# Assignment4B-IR-Sensor_Schematic.net
KiCad netlist of a schematic drawn in EAGLE
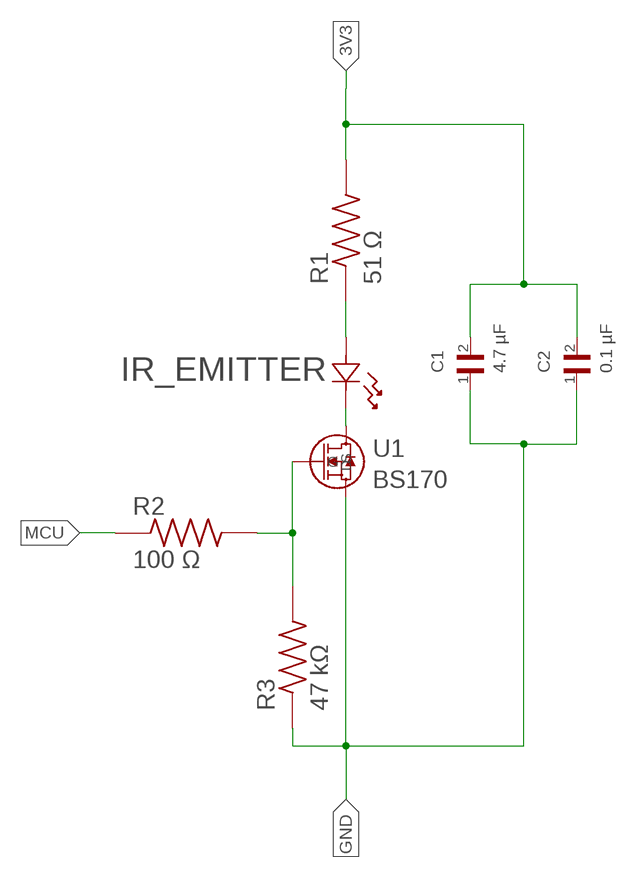
[diagram p0: schematic, sheet 1]

(export (version "E")
  (design (tool "Eeschema 10.0.6"))
  (components
    (comp (ref "C1")
      (value "4.7 µF")
      (footprint "eagle-import:CAPC2012X140N")
      (fields
        (field (name "DIGIKEY_PART_NUMBER") "490-14466-2-ND")
        (field (name "MF") "Murata Electronics")
        (field (name "MP") "GRM21BR71C475KE51L")
      )
      (libsource (lib "eagle-import") (part "GRM21BR71C475KE51L"))
    )
    (comp (ref "C2")
      (value "0.1 µF")
      (footprint "eagle-import:CAPC2012X140N")
      (fields (field (name "MF") "Murata") (field (name "MP") "GCM21BR72A104KA37K"))
      (libsource (lib "eagle-import") (part "GCM21BR72A104KA37K"))
    )
    (comp (ref "LED1")
      (value "IR_EMITTER")
      (footprint "eagle-import:LED_INL-5AMIR15_INO")
      (fields
        (field (name "MANUFACTURER_PART_NUMBER") "INL-5AMIR15")
        (field (name "COPYRIGHT") "Copyright (C) 2024 Ultra Librarian. All rights reserved.")
      )
      (libsource (lib "eagle-import") (part "INL-5AMIR15"))
    )
    (comp (ref "R1")
      (value "51 Ω")
      (footprint "eagle-import:RESC2012X60N")
      (fields
        (field (name "DIGIKEY_PART_NUMBER") "541-51.0TTR-ND")
        (field (name "MF") "Vishay")
        (field (name "MP") "CRCW080551R0FKEAHP")
      )
      (libsource (lib "eagle-import") (part "CRCW080551R0FKEAHP"))
    )
    (comp (ref "R2")
      (value "100 Ω")
      (footprint "eagle-import:RESC2012X60N")
      (fields
        (field (name "DIGIKEY_PART_NUMBER") "541-100TTR-ND")
        (field (name "MF") "Vishay")
        (field (name "MP") "CRCW0805100RFKEAHP")
      )
      (libsource (lib "eagle-import") (part "CRCW0805100RFKEAHP"))
    )
    (comp (ref "R3")
      (value "47 kΩ")
      (footprint "eagle-import:RESC2012X50N")
      (fields
        (field (name "DIGIKEY_PART_NUMBER") "541-47KATR-ND")
        (field (name "MF") "Vishay Dale")
        (field (name "MP") "CRCW080547K0JNEA")
      )
      (libsource (lib "eagle-import") (part "CRCW080547K0JNEA"))
    )
    (comp (ref "U1")
      (value "BS170")
      (footprint "eagle-import:TO_SA06_ONS")
      (fields (field (name "COPYRIGHT") "Copyright (C) 2024 Ultra Librarian. All rights reserved."))
      (libsource (lib "eagle-import") (part "BS170"))
    )
  )
  (nets
    (net (code "1") (name "3V3") (class "Default")
      (node (ref "C1") (pin "2") (pinfunction "2_2") (pintype "passive"))
      (node (ref "C2") (pin "2") (pinfunction "2_2") (pintype "passive"))
      (node (ref "R1") (pin "2") (pinfunction "2_2") (pintype "passive"))
    )
    (net (code "2") (name "GND") (class "Default")
      (node (ref "C1") (pin "1") (pinfunction "1_1") (pintype "passive"))
      (node (ref "C2") (pin "1") (pinfunction "1_1") (pintype "passive"))
      (node (ref "R3") (pin "1") (pinfunction "1_1") (pintype "passive"))
      (node (ref "U1") (pin "3") (pinfunction "S_3") (pintype "passive"))
    )
    (net (code "3") (name "MCU") (class "Default")
      (node (ref "R2") (pin "1") (pinfunction "1_1") (pintype "passive"))
    )
    (net (code "4") (name "Net-(LED1-Pad2)") (class "Default")
      (node (ref "LED1") (pin "2") (pinfunction "2_2") (pintype "passive"))
      (node (ref "R1") (pin "1") (pinfunction "1_1") (pintype "passive"))
    )
    (net (code "5") (name "Net-(U1-D)") (class "Default")
      (node (ref "LED1") (pin "1") (pinfunction "1_1") (pintype "passive"))
      (node (ref "U1") (pin "2") (pinfunction "D_2") (pintype "passive"))
    )
    (net (code "6") (name "Net-(U1-G)") (class "Default")
      (node (ref "R2") (pin "2") (pinfunction "2_2") (pintype "passive"))
      (node (ref "R3") (pin "2") (pinfunction "2_2") (pintype "passive"))
      (node (ref "U1") (pin "1") (pinfunction "G_1") (pintype "passive"))
    )
  )
)
